# v_regulator.net
KiCad netlist of a schematic drawn in EAGLE
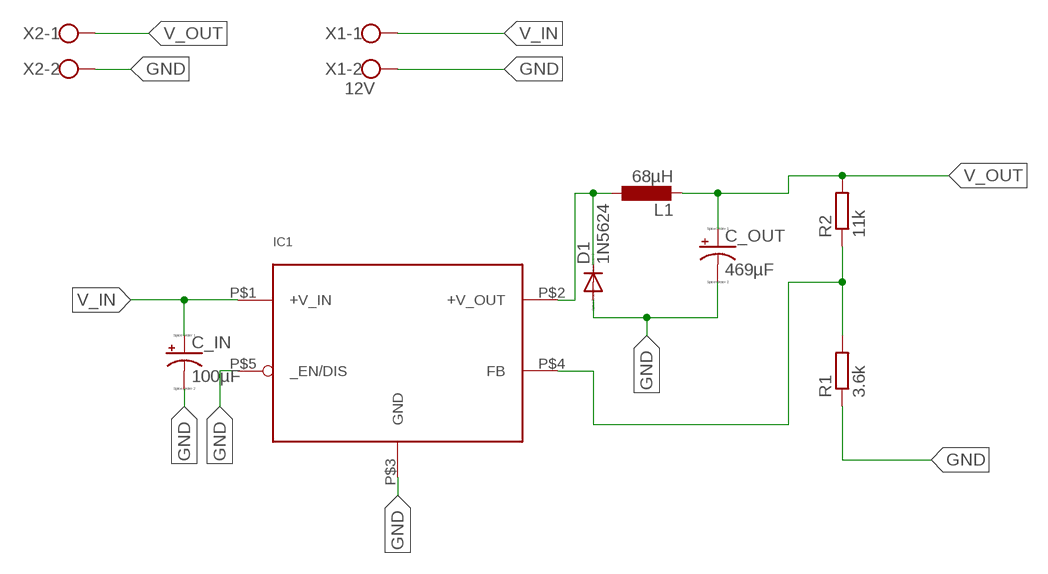
[diagram p0: schematic, sheet 1]

(export (version "E")
  (design (tool "Eeschema 10.0.6"))
  (components
    (comp (ref "C_IN")
      (value "100µF")
      (footprint "eagle-import:E2,5-5")
      (libsource (lib "eagle-import") (part "CPOL-USE2.5-5"))
    )
    (comp (ref "C_OUT")
      (value "469µF")
      (footprint "eagle-import:E2,5-5")
      (libsource (lib "eagle-import") (part "CPOL-USE2.5-5"))
    )
    (comp (ref "D1")
      (value "1N5624")
      (footprint "eagle-import:DO201-15")
      (libsource (lib "eagle-import") (part "1N5624"))
    )
    (comp (ref "IC1")
      (value "LM2576-T05D")
      (footprint "eagle-import:TO220-5_STAGGERED")
      (libsource (lib "eagle-import") (part "LM2576-T05D"))
    )
    (comp (ref "L1")
      (value "68µH")
      (footprint "eagle-import:6000-XXXX-RC")
      (libsource (lib "eagle-import") (part "L-EU6000-XXX-RC"))
    )
    (comp (ref "R1")
      (value "3.6k")
      (footprint "eagle-import:0207_10")
      (libsource (lib "eagle-import") (part "R-EU_0207/10"))
    )
    (comp (ref "R2")
      (value "11k")
      (footprint "eagle-import:0207_10")
      (libsource (lib "eagle-import") (part "R-EU_0207/10"))
    )
    (comp (ref "X1")
      (value "12V")
      (footprint "eagle-import:W237-102")
      (fields (field (name "MPN") "237-102"))
      (libsource (lib "eagle-import") (part "W237-102"))
    )
    (comp (ref "X2")
      (value "W237-102")
      (footprint "eagle-import:W237-102")
      (fields (field (name "MPN") "237-102"))
      (libsource (lib "eagle-import") (part "W237-102"))
    )
  )
  (nets
    (net (code "1") (name "GND") (class "Default")
      (node (ref "C_IN") (pin "-") (pinfunction "-_-") (pintype "passive"))
      (node (ref "C_OUT") (pin "-") (pinfunction "-_-") (pintype "passive"))
      (node (ref "D1") (pin "A") (pinfunction "A_A") (pintype "passive"))
      (node (ref "IC1") (pin "P$3") (pinfunction "GND_P$3") (pintype "power_in"))
      (node (ref "IC1") (pin "P$5") (pinfunction "_EN/DIS_P$5") (pintype "input"))
      (node (ref "R1") (pin "1") (pinfunction "1_1") (pintype "passive"))
      (node (ref "X1") (pin "2") (pinfunction "KL_2") (pintype "passive"))
      (node (ref "X2") (pin "2") (pinfunction "KL_2") (pintype "passive"))
    )
    (net (code "2") (name "Net-(IC1-+V_OUT)") (class "Default")
      (node (ref "D1") (pin "C") (pinfunction "C_C") (pintype "passive"))
      (node (ref "IC1") (pin "P$2") (pinfunction "+V_OUT_P$2") (pintype "output"))
      (node (ref "L1") (pin "1") (pinfunction "1_1") (pintype "passive"))
    )
    (net (code "3") (name "Net-(IC1-FB)") (class "Default")
      (node (ref "IC1") (pin "P$4") (pinfunction "FB_P$4") (pintype "input"))
      (node (ref "R1") (pin "2") (pinfunction "2_2") (pintype "passive"))
      (node (ref "R2") (pin "1") (pinfunction "1_1") (pintype "passive"))
    )
    (net (code "4") (name "V_IN") (class "Default")
      (node (ref "C_IN") (pin "+") (pinfunction "+_+") (pintype "passive"))
      (node (ref "IC1") (pin "P$1") (pinfunction "+V_IN_P$1") (pintype "input"))
      (node (ref "X1") (pin "1") (pinfunction "KL_1") (pintype "passive"))
    )
    (net (code "5") (name "V_OUT") (class "Default")
      (node (ref "C_OUT") (pin "+") (pinfunction "+_+") (pintype "passive"))
      (node (ref "L1") (pin "2") (pinfunction "2_2") (pintype "passive"))
      (node (ref "R2") (pin "2") (pinfunction "2_2") (pintype "passive"))
      (node (ref "X2") (pin "1") (pinfunction "KL_1") (pintype "passive"))
    )
  )
)
